# nrf24L01Sheild.net
KiCad netlist of a schematic drawn in EAGLE
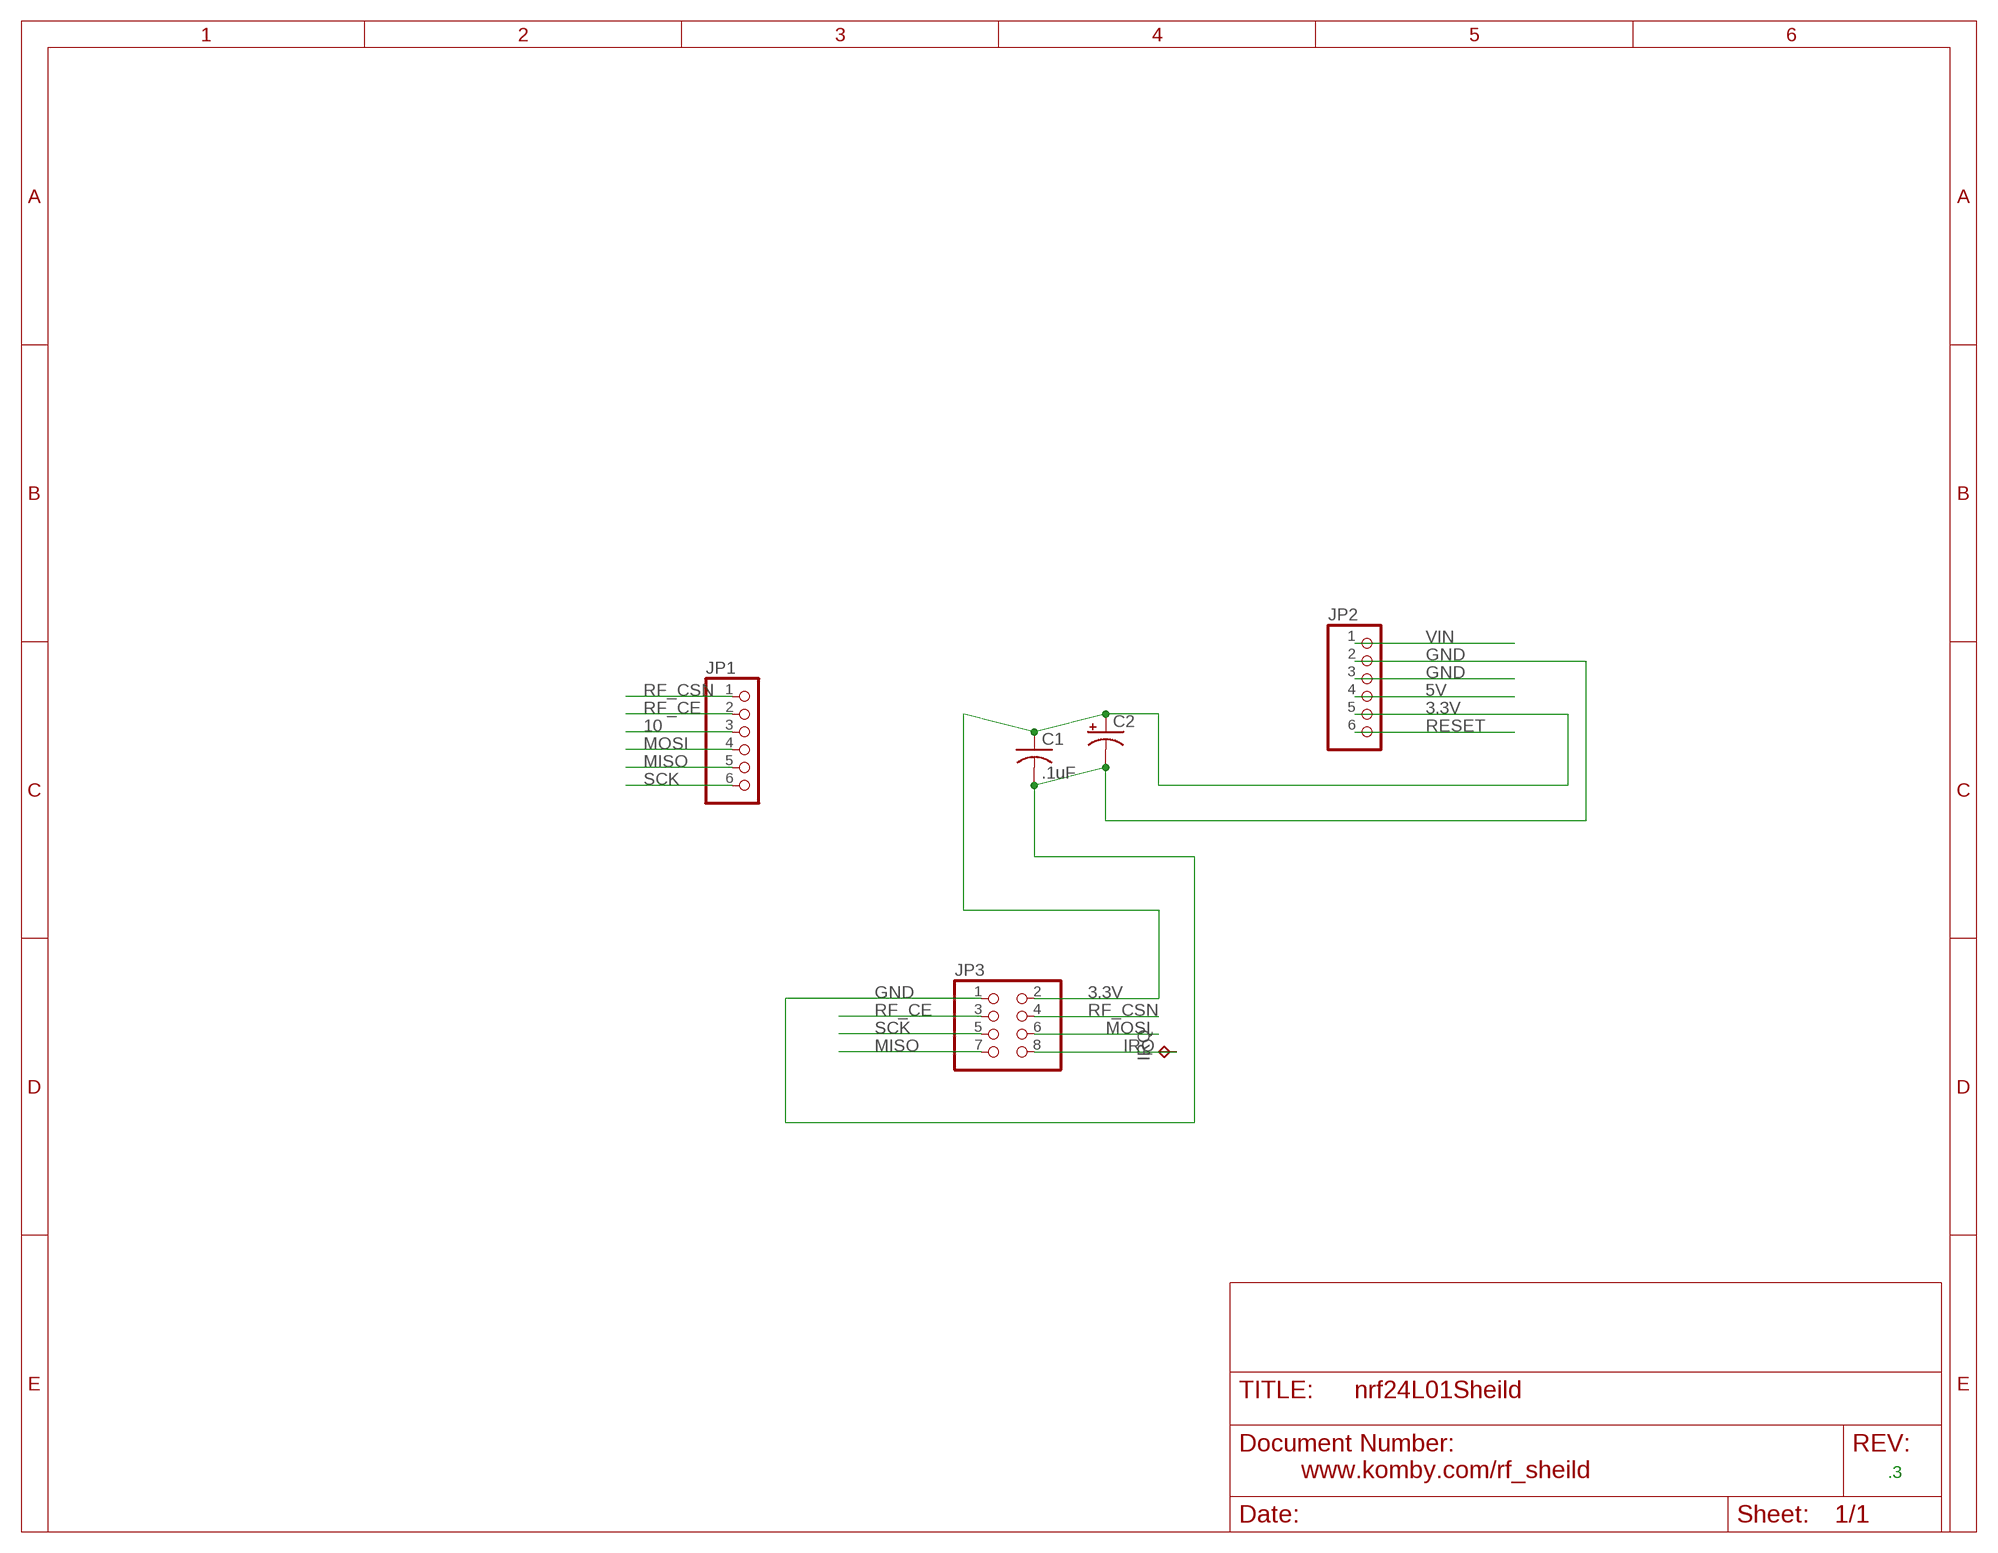
[diagram p0: schematic, sheet 1]

(export (version "E")
  (design (tool "Eeschema 10.0.6"))
  (components
    (comp (ref "C1")
      (value ".1uF")
      (footprint "eagle-import:C025-024X044")
      (libsource (lib "eagle-import") (part "C-US025-024X044"))
    )
    (comp (ref "C2")
      (value "CPOL-USE2.5-6")
      (footprint "eagle-import:E2,5-6")
      (libsource (lib "eagle-import") (part "CPOL-USE2.5-6"))
    )
    (comp (ref "IRQ")
      (value "IRQ")
      (footprint "eagle-import:P1-13")
      (libsource (lib "eagle-import") (part "TPPAD1-13"))
    )
    (comp (ref "JP1")
      (value "PINHD-1X6B")
      (footprint "eagle-import:1X06-BIG")
      (libsource (lib "eagle-import") (part "PINHD-1X6B"))
    )
    (comp (ref "JP2")
      (value "PINHD-1X6B")
      (footprint "eagle-import:1X06-BIG")
      (libsource (lib "eagle-import") (part "PINHD-1X6B"))
    )
    (comp (ref "JP3")
      (value "PINHD-2X4")
      (footprint "eagle-import:2X04")
      (libsource (lib "eagle-import") (part "PINHD-2X4"))
    )
  )
  (nets
    (net (code "1") (name "/3.3V") (class "Default")
      (node (ref "C1") (pin "1") (pinfunction "1_1") (pintype "passive"))
      (node (ref "C2") (pin "+") (pinfunction "+_+") (pintype "passive"))
      (node (ref "JP2") (pin "5") (pinfunction "5_5") (pintype "passive"))
      (node (ref "JP3") (pin "2") (pinfunction "2_2") (pintype "passive"))
    )
    (net (code "2") (name "/5V") (class "Default")
      (node (ref "JP2") (pin "4") (pinfunction "4_4") (pintype "passive"))
    )
    (net (code "3") (name "/10") (class "Default")
      (node (ref "JP1") (pin "3") (pinfunction "3_3") (pintype "passive"))
    )
    (net (code "4") (name "/GND") (class "Default")
      (node (ref "C1") (pin "2") (pinfunction "2_2") (pintype "passive"))
      (node (ref "C2") (pin "-") (pinfunction "-_-") (pintype "passive"))
      (node (ref "JP2") (pin "2") (pinfunction "2_2") (pintype "passive"))
      (node (ref "JP2") (pin "3") (pinfunction "3_3") (pintype "passive"))
      (node (ref "JP3") (pin "1") (pinfunction "1_1") (pintype "passive"))
    )
    (net (code "5") (name "/IRQ") (class "Default")
      (node (ref "IRQ") (pin "TP") (pinfunction "TP_TP") (pintype "input"))
      (node (ref "JP3") (pin "8") (pinfunction "8_8") (pintype "passive"))
    )
    (net (code "6") (name "/MISO") (class "Default")
      (node (ref "JP1") (pin "5") (pinfunction "5_5") (pintype "passive"))
      (node (ref "JP3") (pin "7") (pinfunction "7_7") (pintype "passive"))
    )
    (net (code "7") (name "/MOSI") (class "Default")
      (node (ref "JP1") (pin "4") (pinfunction "4_4") (pintype "passive"))
      (node (ref "JP3") (pin "6") (pinfunction "6_6") (pintype "passive"))
    )
    (net (code "8") (name "/RESET") (class "Default")
      (node (ref "JP2") (pin "6") (pinfunction "6_6") (pintype "passive"))
    )
    (net (code "9") (name "/RF_CE") (class "Default")
      (node (ref "JP1") (pin "2") (pinfunction "2_2") (pintype "passive"))
      (node (ref "JP3") (pin "3") (pinfunction "3_3") (pintype "passive"))
    )
    (net (code "10") (name "/RF_CSN") (class "Default")
      (node (ref "JP1") (pin "1") (pinfunction "1_1") (pintype "passive"))
      (node (ref "JP3") (pin "4") (pinfunction "4_4") (pintype "passive"))
    )
    (net (code "11") (name "/SCK") (class "Default")
      (node (ref "JP1") (pin "6") (pinfunction "6_6") (pintype "passive"))
      (node (ref "JP3") (pin "5") (pinfunction "5_5") (pintype "passive"))
    )
    (net (code "12") (name "/VIN") (class "Default")
      (node (ref "JP2") (pin "1") (pinfunction "1_1") (pintype "passive"))
    )
  )
)
